# 001-0001_Christmas_Ornament.net
KiCad netlist of a schematic drawn in Altium Designer
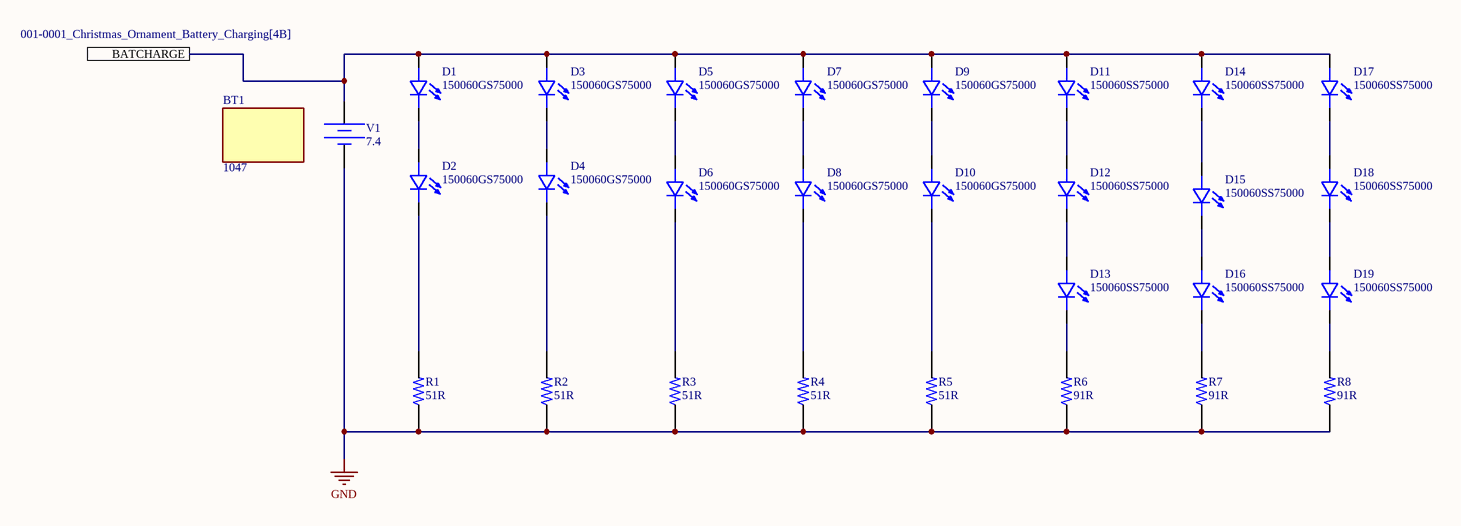
[diagram p0: 001-0001_Christmas_Ornament.SchDoc]

(export (version "E")
  (design (tool "Eeschema 10.0.6"))
  (components
    (comp (ref "BT1")
      (value "1047")
      (footprint "BAT_1047")
      (description "18650 Dual Battery Holder")
      (libsource (lib "default") (part "1047"))
    )
    (comp (ref "D1")
      (value "150060GS75000")
      (footprint "LEDC1608X80N")
      (description "Green 520nm LED Indication - Discrete 3.2V 0603 (1608 Metric)")
      (fields (field (name "MF") "Wurth Electronics"))
      (libsource (lib "default") (part "150060GS75000"))
    )
    (comp (ref "D2")
      (value "150060GS75000")
      (footprint "LEDC1608X80N")
      (description "Green 520nm LED Indication - Discrete 3.2V 0603 (1608 Metric)")
      (fields (field (name "MF") "Wurth Electronics"))
      (libsource (lib "default") (part "150060GS75000"))
    )
    (comp (ref "D3")
      (value "150060GS75000")
      (footprint "LEDC1608X80N")
      (description "Green 520nm LED Indication - Discrete 3.2V 0603 (1608 Metric)")
      (fields (field (name "MF") "Wurth Electronics"))
      (libsource (lib "default") (part "150060GS75000"))
    )
    (comp (ref "D4")
      (value "150060GS75000")
      (footprint "LEDC1608X80N")
      (description "Green 520nm LED Indication - Discrete 3.2V 0603 (1608 Metric)")
      (fields (field (name "MF") "Wurth Electronics"))
      (libsource (lib "default") (part "150060GS75000"))
    )
    (comp (ref "D5")
      (value "150060GS75000")
      (footprint "LEDC1608X80N")
      (description "Green 520nm LED Indication - Discrete 3.2V 0603 (1608 Metric)")
      (fields (field (name "MF") "Wurth Electronics"))
      (libsource (lib "default") (part "150060GS75000"))
    )
    (comp (ref "D6")
      (value "150060GS75000")
      (footprint "LEDC1608X80N")
      (description "Green 520nm LED Indication - Discrete 3.2V 0603 (1608 Metric)")
      (fields (field (name "MF") "Wurth Electronics"))
      (libsource (lib "default") (part "150060GS75000"))
    )
    (comp (ref "D7")
      (value "150060GS75000")
      (footprint "LEDC1608X80N")
      (description "Green 520nm LED Indication - Discrete 3.2V 0603 (1608 Metric)")
      (fields (field (name "MF") "Wurth Electronics"))
      (libsource (lib "default") (part "150060GS75000"))
    )
    (comp (ref "D8")
      (value "150060GS75000")
      (footprint "LEDC1608X80N")
      (description "Green 520nm LED Indication - Discrete 3.2V 0603 (1608 Metric)")
      (fields (field (name "MF") "Wurth Electronics"))
      (libsource (lib "default") (part "150060GS75000"))
    )
    (comp (ref "D9")
      (value "150060GS75000")
      (footprint "LEDC1608X80N")
      (description "Green 520nm LED Indication - Discrete 3.2V 0603 (1608 Metric)")
      (fields (field (name "MF") "Wurth Electronics"))
      (libsource (lib "default") (part "150060GS75000"))
    )
    (comp (ref "D10")
      (value "150060GS75000")
      (footprint "LEDC1608X80N")
      (description "Green 520nm LED Indication - Discrete 3.2V 0603 (1608 Metric)")
      (fields (field (name "MF") "Wurth Electronics"))
      (libsource (lib "default") (part "150060GS75000"))
    )
    (comp (ref "D11")
      (value "150060SS75000")
      (footprint "LED_150060SS75000")
      (fields (field (name "MF") "{'manufacturer': u'Wurth Electronics'}"))
      (libsource (lib "default") (part "150060SS75000"))
    )
    (comp (ref "D12")
      (value "150060SS75000")
      (footprint "LED_150060SS75000")
      (fields (field (name "MF") "{'manufacturer': u'Wurth Electronics'}"))
      (libsource (lib "default") (part "150060SS75000"))
    )
    (comp (ref "D13")
      (value "150060SS75000")
      (footprint "LED_150060SS75000")
      (fields (field (name "MF") "{'manufacturer': u'Wurth Electronics'}"))
      (libsource (lib "default") (part "150060SS75000"))
    )
    (comp (ref "D14")
      (value "150060SS75000")
      (footprint "LED_150060SS75000")
      (fields (field (name "MF") "{'manufacturer': u'Wurth Electronics'}"))
      (libsource (lib "default") (part "150060SS75000"))
    )
    (comp (ref "D15")
      (value "150060SS75000")
      (footprint "LED_150060SS75000")
      (fields (field (name "MF") "{'manufacturer': u'Wurth Electronics'}"))
      (libsource (lib "default") (part "150060SS75000"))
    )
    (comp (ref "D16")
      (value "150060SS75000")
      (footprint "LED_150060SS75000")
      (fields (field (name "MF") "{'manufacturer': u'Wurth Electronics'}"))
      (libsource (lib "default") (part "150060SS75000"))
    )
    (comp (ref "D17")
      (value "150060SS75000")
      (footprint "LED_150060SS75000")
      (fields (field (name "MF") "{'manufacturer': u'Wurth Electronics'}"))
      (libsource (lib "default") (part "150060SS75000"))
    )
    (comp (ref "D18")
      (value "150060SS75000")
      (footprint "LED_150060SS75000")
      (fields (field (name "MF") "{'manufacturer': u'Wurth Electronics'}"))
      (libsource (lib "default") (part "150060SS75000"))
    )
    (comp (ref "D19")
      (value "150060SS75000")
      (footprint "LED_150060SS75000")
      (fields (field (name "MF") "{'manufacturer': u'Wurth Electronics'}"))
      (libsource (lib "default") (part "150060SS75000"))
    )
    (comp (ref "R1")
      (value "51R")
      (footprint "default:ERJ-PA3F51R0V")
      (description "RES SMD 51 OHM 1% 1/3W 0603")
      (fields (field (name "MP") "ERJPA3F51R0V"))
      (libsource (lib "default") (part "ERJ-PA3F51R0V"))
    )
    (comp (ref "R2")
      (value "51R")
      (footprint "default:ERJ-PA3F51R0V")
      (description "RES SMD 51 OHM 1% 1/3W 0603")
      (fields (field (name "MP") "ERJPA3F51R0V"))
      (libsource (lib "default") (part "ERJ-PA3F51R0V"))
    )
    (comp (ref "R3")
      (value "51R")
      (footprint "default:ERJ-PA3F51R0V")
      (description "RES SMD 51 OHM 1% 1/3W 0603")
      (fields (field (name "MP") "ERJPA3F51R0V"))
      (libsource (lib "default") (part "ERJ-PA3F51R0V"))
    )
    (comp (ref "R4")
      (value "51R")
      (footprint "default:ERJ-PA3F51R0V")
      (description "RES SMD 51 OHM 1% 1/3W 0603")
      (fields (field (name "MP") "ERJPA3F51R0V"))
      (libsource (lib "default") (part "ERJ-PA3F51R0V"))
    )
    (comp (ref "R5")
      (value "51R")
      (footprint "default:ERJ-PA3F51R0V")
      (description "RES SMD 51 OHM 1% 1/3W 0603")
      (fields (field (name "MP") "ERJPA3F51R0V"))
      (libsource (lib "default") (part "ERJ-PA3F51R0V"))
    )
    (comp (ref "R6")
      (value "91R")
      (footprint "default:ERJ-PA3F91R0V")
      (description "RES SMD 91 OHM 1% 1/3W 0603")
      (fields (field (name "MP") "ERJPA3F91R0V"))
      (libsource (lib "default") (part "ERJ-PA3F91R0V"))
    )
    (comp (ref "R7")
      (value "91R")
      (footprint "default:ERJ-PA3F91R0V")
      (description "RES SMD 91 OHM 1% 1/3W 0603")
      (fields (field (name "MP") "ERJPA3F91R0V"))
      (libsource (lib "default") (part "ERJ-PA3F91R0V"))
    )
    (comp (ref "R8")
      (value "91R")
      (footprint "default:ERJ-PA3F91R0V")
      (description "RES SMD 91 OHM 1% 1/3W 0603")
      (fields (field (name "MP") "ERJPA3F91R0V"))
      (libsource (lib "default") (part "ERJ-PA3F91R0V"))
    )
    (comp (ref "V1")
      (value "Constant Voltage Source")
      (fields (field (name "DC MAGNITUDE") "7.4"))
      (libsource (lib "Simulation Generic Components") (part "Battery"))
    )
  )
  (nets
    (net (code "1") (name "/BATCHARGE") (class "Default")
      (node (ref "D1") (pin "A") (pinfunction "A_A") (pintype "passive"))
      (node (ref "D11") (pin "A") (pinfunction "A_A") (pintype "passive"))
      (node (ref "D14") (pin "A") (pinfunction "A_A") (pintype "passive"))
      (node (ref "D17") (pin "A") (pinfunction "A_A") (pintype "passive"))
      (node (ref "D3") (pin "A") (pinfunction "A_A") (pintype "passive"))
      (node (ref "D5") (pin "A") (pinfunction "A_A") (pintype "passive"))
      (node (ref "D7") (pin "A") (pinfunction "A_A") (pintype "passive"))
      (node (ref "D9") (pin "A") (pinfunction "A_A") (pintype "passive"))
      (node (ref "V1") (pin "1") (pinfunction "1_1") (pintype "passive"))
    )
    (net (code "2") (name "GND") (class "Default")
      (node (ref "R1") (pin "1") (pinfunction "1_1") (pintype "passive"))
      (node (ref "R2") (pin "1") (pinfunction "1_1") (pintype "passive"))
      (node (ref "R3") (pin "1") (pinfunction "1_1") (pintype "passive"))
      (node (ref "R4") (pin "1") (pinfunction "1_1") (pintype "passive"))
      (node (ref "R5") (pin "1") (pinfunction "1_1") (pintype "passive"))
      (node (ref "R6") (pin "1") (pinfunction "1_1") (pintype "passive"))
      (node (ref "R7") (pin "1") (pinfunction "1_1") (pintype "passive"))
      (node (ref "R8") (pin "1") (pinfunction "1_1") (pintype "passive"))
      (node (ref "V1") (pin "2") (pinfunction "2_2") (pintype "passive"))
    )
    (net (code "3") (name "Net-(D1-PadC)") (class "Default")
      (node (ref "D1") (pin "C") (pinfunction "C_C") (pintype "passive"))
      (node (ref "D2") (pin "A") (pinfunction "A_A") (pintype "passive"))
    )
    (net (code "4") (name "Net-(D2-PadC)") (class "Default")
      (node (ref "D2") (pin "C") (pinfunction "C_C") (pintype "passive"))
      (node (ref "R1") (pin "2") (pinfunction "2_2") (pintype "passive"))
    )
    (net (code "5") (name "Net-(D3-PadC)") (class "Default")
      (node (ref "D3") (pin "C") (pinfunction "C_C") (pintype "passive"))
      (node (ref "D4") (pin "A") (pinfunction "A_A") (pintype "passive"))
    )
    (net (code "6") (name "Net-(D4-PadC)") (class "Default")
      (node (ref "D4") (pin "C") (pinfunction "C_C") (pintype "passive"))
      (node (ref "R2") (pin "2") (pinfunction "2_2") (pintype "passive"))
    )
    (net (code "7") (name "Net-(D5-PadC)") (class "Default")
      (node (ref "D5") (pin "C") (pinfunction "C_C") (pintype "passive"))
      (node (ref "D6") (pin "A") (pinfunction "A_A") (pintype "passive"))
    )
    (net (code "8") (name "Net-(D6-PadC)") (class "Default")
      (node (ref "D6") (pin "C") (pinfunction "C_C") (pintype "passive"))
      (node (ref "R3") (pin "2") (pinfunction "2_2") (pintype "passive"))
    )
    (net (code "9") (name "Net-(D7-PadC)") (class "Default")
      (node (ref "D7") (pin "C") (pinfunction "C_C") (pintype "passive"))
      (node (ref "D8") (pin "A") (pinfunction "A_A") (pintype "passive"))
    )
    (net (code "10") (name "Net-(D8-PadC)") (class "Default")
      (node (ref "D8") (pin "C") (pinfunction "C_C") (pintype "passive"))
      (node (ref "R4") (pin "2") (pinfunction "2_2") (pintype "passive"))
    )
    (net (code "11") (name "Net-(D10-PadA)") (class "Default")
      (node (ref "D10") (pin "A") (pinfunction "A_A") (pintype "passive"))
      (node (ref "D9") (pin "C") (pinfunction "C_C") (pintype "passive"))
    )
    (net (code "12") (name "Net-(D10-PadC)") (class "Default")
      (node (ref "D10") (pin "C") (pinfunction "C_C") (pintype "passive"))
      (node (ref "R5") (pin "2") (pinfunction "2_2") (pintype "passive"))
    )
    (net (code "13") (name "Net-(D11-PadC)") (class "Default")
      (node (ref "D11") (pin "C") (pinfunction "C_C") (pintype "passive"))
      (node (ref "D12") (pin "A") (pinfunction "A_A") (pintype "passive"))
    )
    (net (code "14") (name "Net-(D12-PadC)") (class "Default")
      (node (ref "D12") (pin "C") (pinfunction "C_C") (pintype "passive"))
      (node (ref "D13") (pin "A") (pinfunction "A_A") (pintype "passive"))
    )
    (net (code "15") (name "Net-(D13-PadC)") (class "Default")
      (node (ref "D13") (pin "C") (pinfunction "C_C") (pintype "passive"))
      (node (ref "R6") (pin "2") (pinfunction "2_2") (pintype "passive"))
    )
    (net (code "16") (name "Net-(D14-PadC)") (class "Default")
      (node (ref "D14") (pin "C") (pinfunction "C_C") (pintype "passive"))
      (node (ref "D15") (pin "A") (pinfunction "A_A") (pintype "passive"))
    )
    (net (code "17") (name "Net-(D15-PadC)") (class "Default")
      (node (ref "D15") (pin "C") (pinfunction "C_C") (pintype "passive"))
      (node (ref "D16") (pin "A") (pinfunction "A_A") (pintype "passive"))
    )
    (net (code "18") (name "Net-(D16-PadC)") (class "Default")
      (node (ref "D16") (pin "C") (pinfunction "C_C") (pintype "passive"))
      (node (ref "R7") (pin "2") (pinfunction "2_2") (pintype "passive"))
    )
    (net (code "19") (name "Net-(D17-PadC)") (class "Default")
      (node (ref "D17") (pin "C") (pinfunction "C_C") (pintype "passive"))
      (node (ref "D18") (pin "A") (pinfunction "A_A") (pintype "passive"))
    )
    (net (code "20") (name "Net-(D18-PadC)") (class "Default")
      (node (ref "D18") (pin "C") (pinfunction "C_C") (pintype "passive"))
      (node (ref "D19") (pin "A") (pinfunction "A_A") (pintype "passive"))
    )
    (net (code "21") (name "Net-(D19-PadC)") (class "Default")
      (node (ref "D19") (pin "C") (pinfunction "C_C") (pintype "passive"))
      (node (ref "R8") (pin "2") (pinfunction "2_2") (pintype "passive"))
    )
  )
)
